# Grove_-_Vibrator_Motor_v1_2.net
KiCad netlist of a schematic drawn in EAGLE
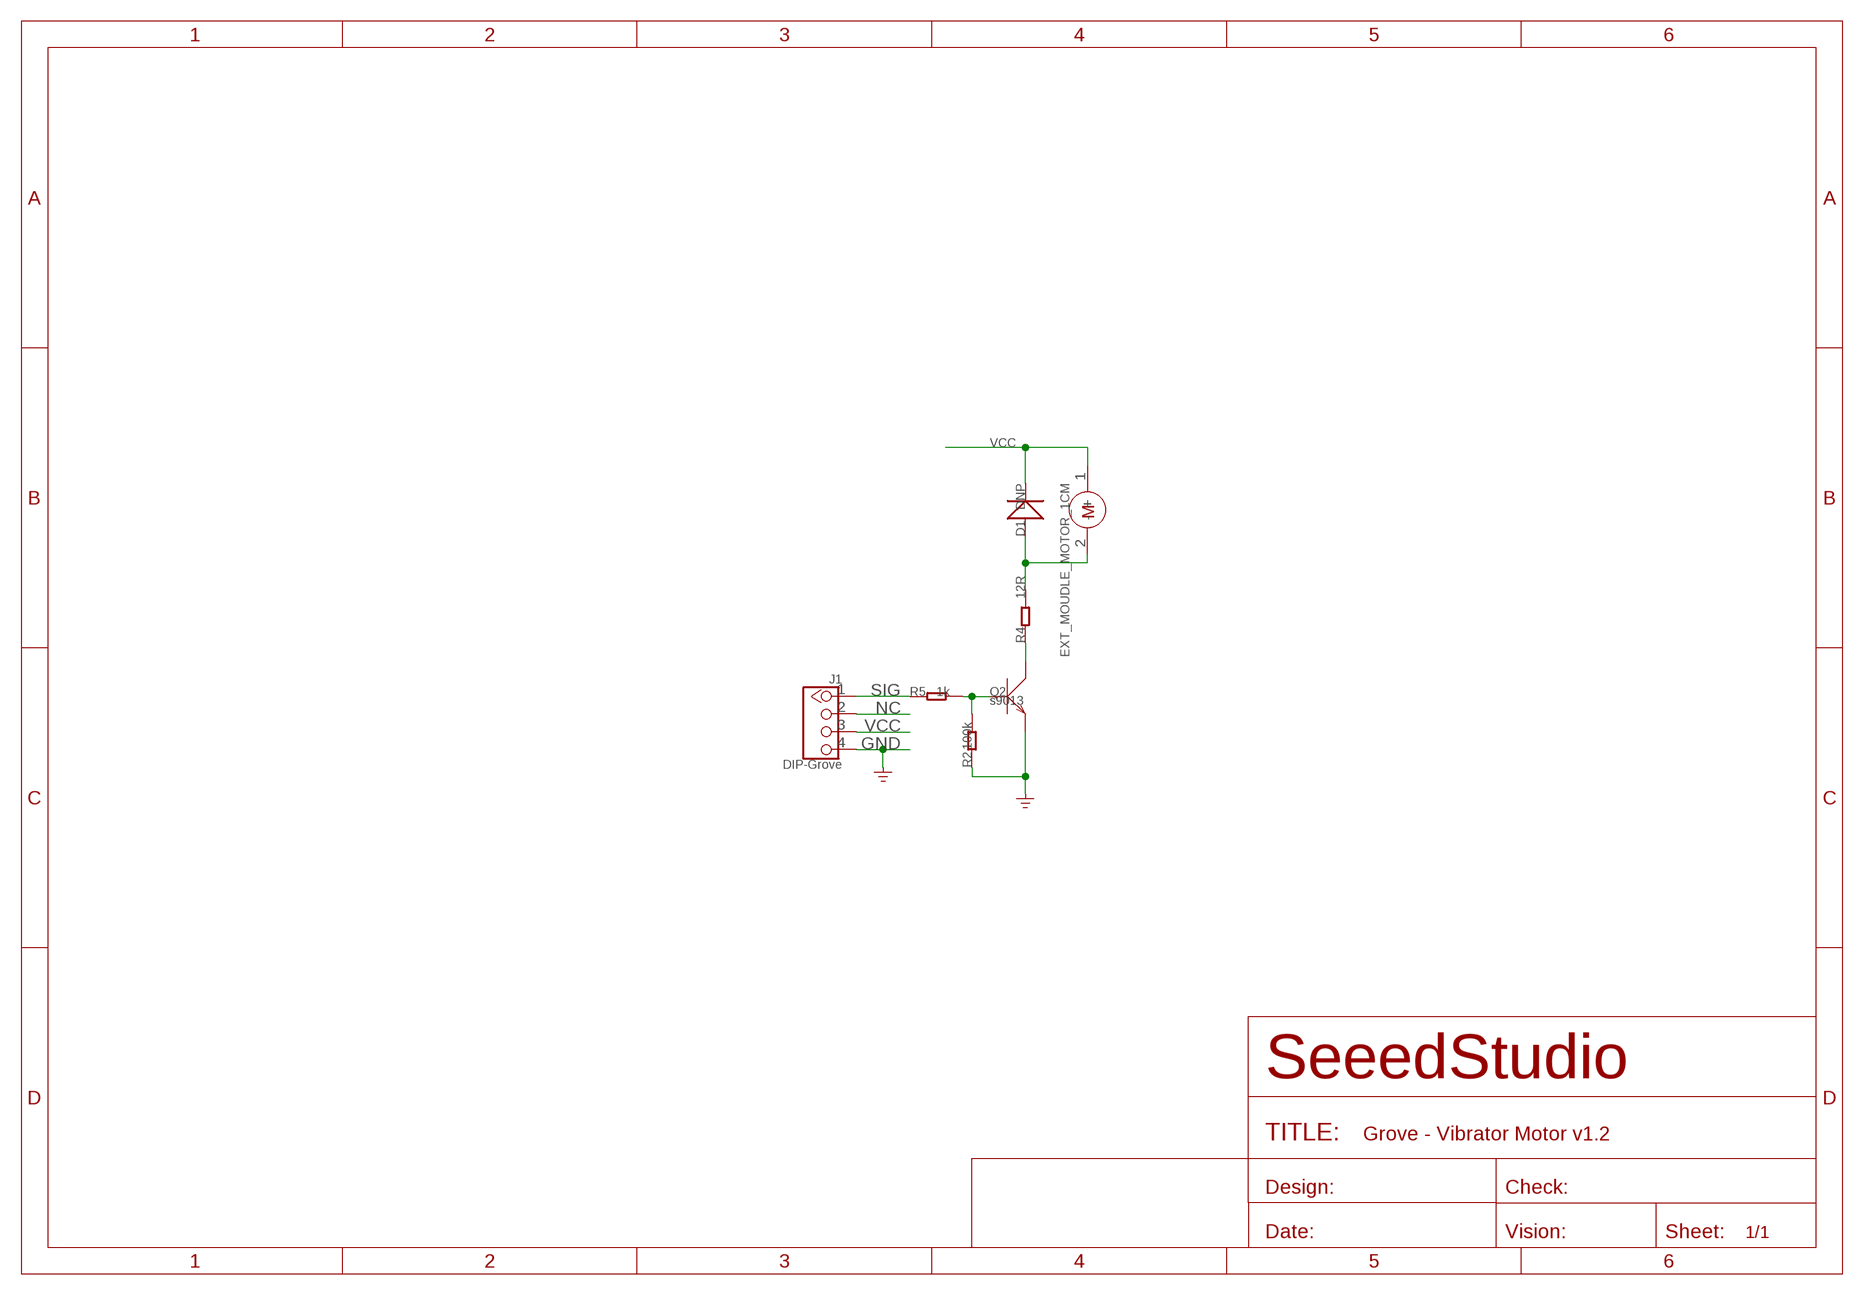
[diagram p0: schematic, sheet 1]

(export (version "E")
  (design (tool "Eeschema 10.0.6"))
  (components
    (comp (ref "D1")
      (value "DNP")
      (footprint "eagle-import:SOD123")
      (libsource (lib "eagle-import") (part "D'1206'"))
    )
    (comp (ref "J1")
      (value "DIP-Grove")
      (footprint "eagle-import:2.0_1X4")
      (libsource (lib "eagle-import") (part "TWIG_2.0-DIP-FEMALE"))
    )
    (comp (ref "M1")
      (value "EXT_MOUDLE_MOTOR_1CM")
      (footprint "eagle-import:EXT_MOUDLE_MOTOR_1CM")
      (libsource (lib "eagle-import") (part "EXT_MOUDLE_MOTOR_1CM"))
    )
    (comp (ref "Q2")
      (value "s9013")
      (footprint "eagle-import:SOT23")
      (libsource (lib "eagle-import") (part "TRANSISTOR-NPN-SOT23"))
    )
    (comp (ref "R2")
      (value "100k")
      (footprint "eagle-import:R0603")
      (libsource (lib "eagle-import") (part "R-0603"))
    )
    (comp (ref "R4")
      (value "12R")
      (footprint "eagle-import:R0603")
      (libsource (lib "eagle-import") (part "R-0603"))
    )
    (comp (ref "R5")
      (value "1k")
      (footprint "eagle-import:R0603")
      (libsource (lib "eagle-import") (part "R-0603"))
    )
  )
  (nets
    (net (code "1") (name "/NC") (class "Default")
      (node (ref "J1") (pin "2") (pinfunction "2_2") (pintype "bidirectional"))
    )
    (net (code "2") (name "/SIG") (class "Default")
      (node (ref "J1") (pin "1") (pinfunction "1_1") (pintype "bidirectional"))
      (node (ref "R5") (pin "1") (pinfunction "1_1") (pintype "passive"))
    )
    (net (code "3") (name "/VCC") (class "Default")
      (node (ref "D1") (pin "-") (pinfunction "-_-") (pintype "passive"))
      (node (ref "J1") (pin "3") (pinfunction "3_3") (pintype "bidirectional"))
      (node (ref "M1") (pin "1") (pinfunction "+_1") (pintype "bidirectional"))
    )
    (net (code "4") (name "GND_POWER") (class "Default")
      (node (ref "J1") (pin "4") (pinfunction "4_4") (pintype "bidirectional"))
      (node (ref "Q2") (pin "2") (pinfunction "E_2") (pintype "passive"))
      (node (ref "R2") (pin "1") (pinfunction "1_1") (pintype "passive"))
    )
    (net (code "5") (name "Net-(M1--)") (class "Default")
      (node (ref "D1") (pin "+") (pinfunction "+_+") (pintype "passive"))
      (node (ref "M1") (pin "2") (pinfunction "-_2") (pintype "bidirectional"))
      (node (ref "R4") (pin "2") (pinfunction "2_2") (pintype "passive"))
    )
    (net (code "6") (name "Net-(Q2-B)") (class "Default")
      (node (ref "Q2") (pin "1") (pinfunction "B_1") (pintype "passive"))
      (node (ref "R2") (pin "2") (pinfunction "2_2") (pintype "passive"))
      (node (ref "R5") (pin "2") (pinfunction "2_2") (pintype "passive"))
    )
    (net (code "7") (name "Net-(Q2-C)") (class "Default")
      (node (ref "Q2") (pin "3") (pinfunction "C_3") (pintype "passive"))
      (node (ref "R4") (pin "1") (pinfunction "1_1") (pintype "passive"))
    )
  )
)
